# hifiberry_breakout.net
KiCad netlist of a schematic drawn in EAGLE
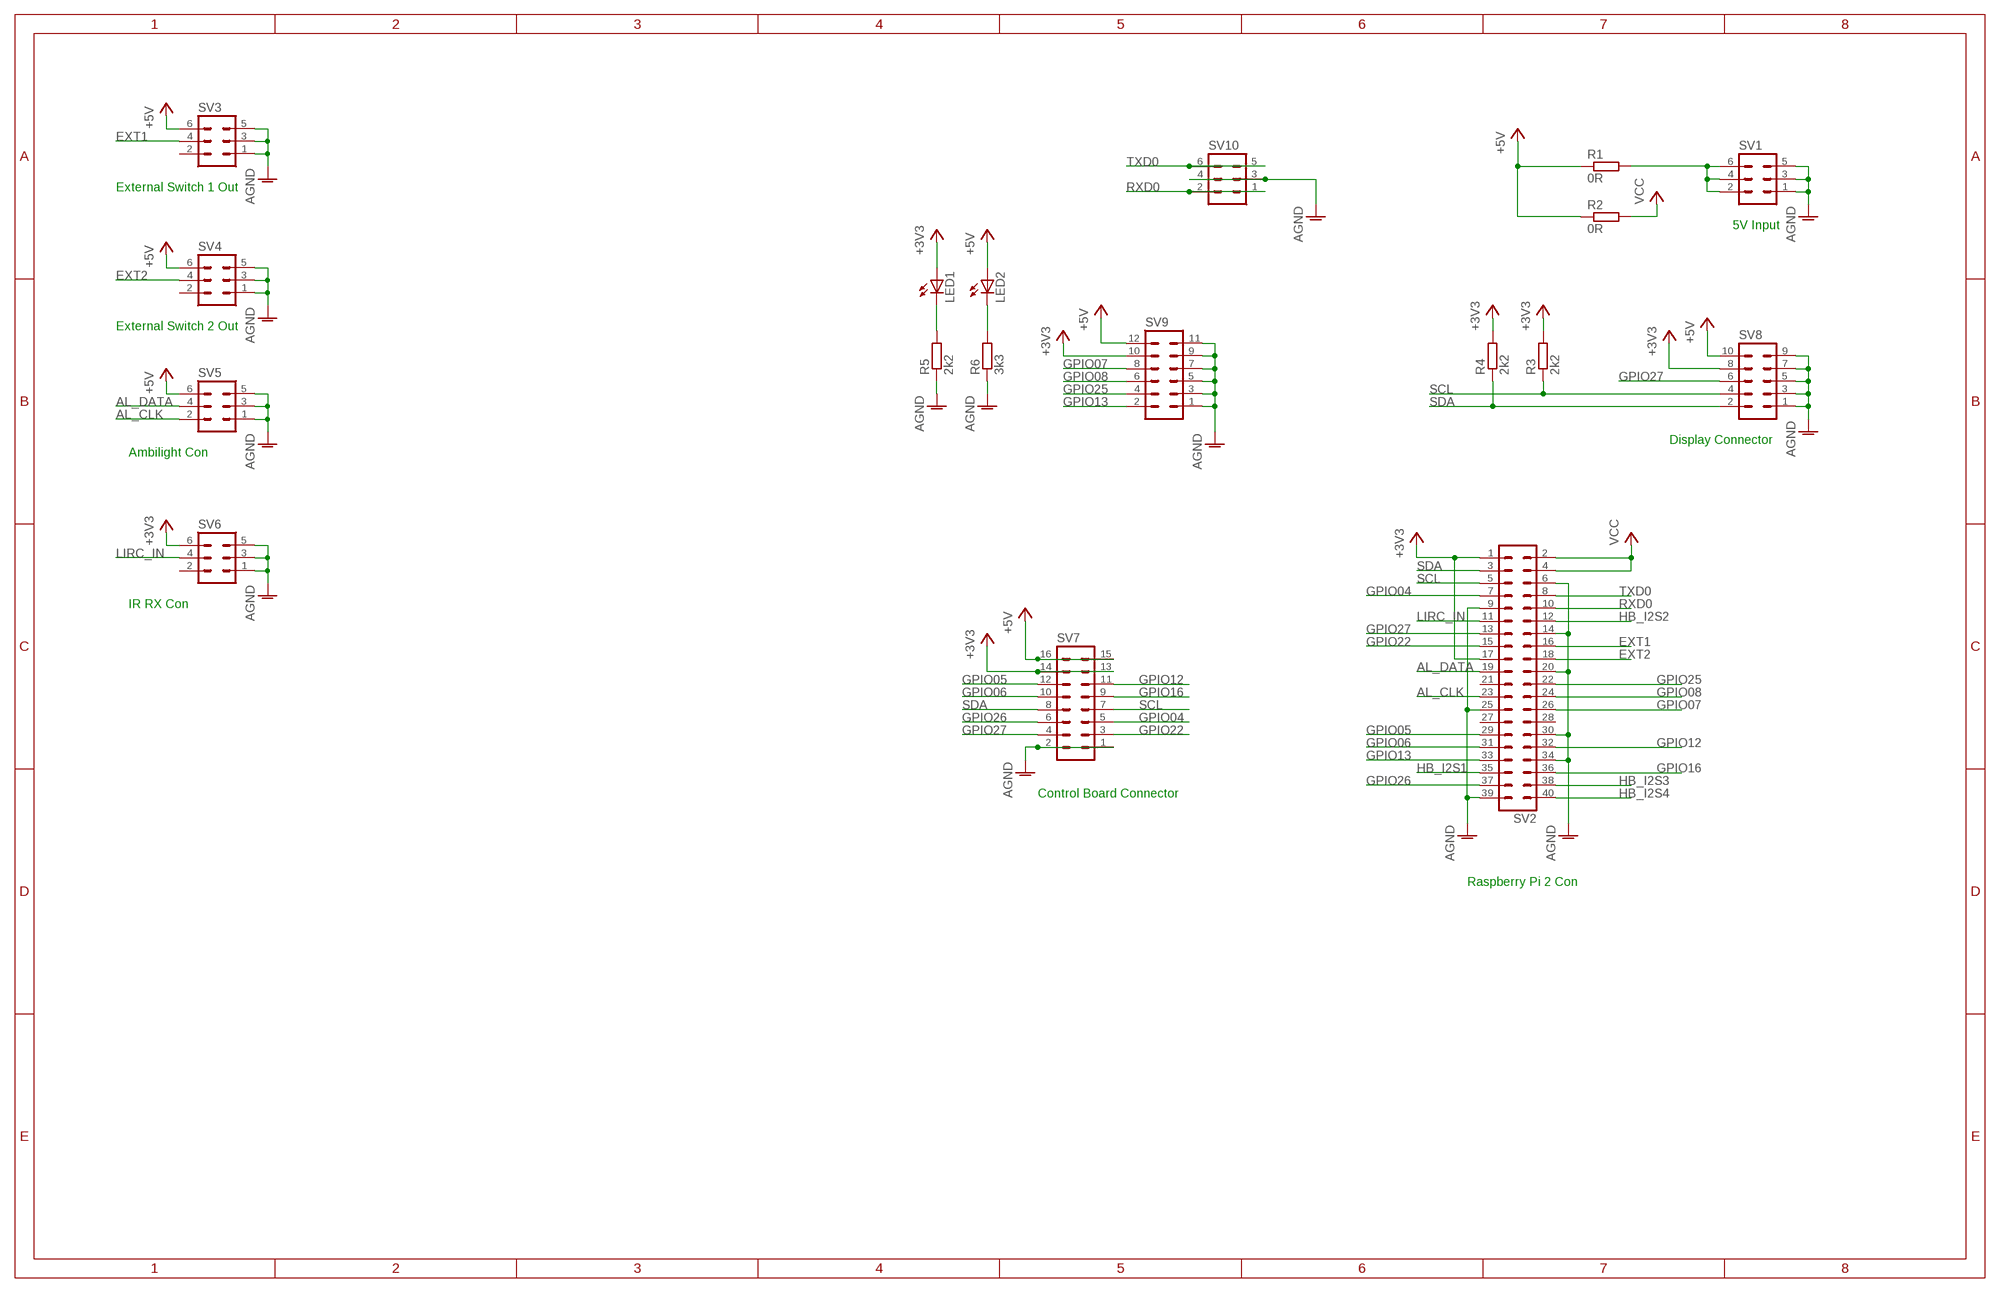
[diagram p0: schematic, sheet 1]

(export (version "E")
  (design (tool "Eeschema 10.0.6"))
  (components
    (comp (ref "LED1")
      (value "LEDCHIPLED_0603")
      (footprint "eagle-import:CHIPLED_0603")
      (libsource (lib "eagle-import") (part "LEDCHIPLED_0603"))
    )
    (comp (ref "LED2")
      (value "LEDCHIPLED_0603")
      (footprint "eagle-import:CHIPLED_0603")
      (libsource (lib "eagle-import") (part "LEDCHIPLED_0603"))
    )
    (comp (ref "R1")
      (value "0R")
      (footprint "eagle-import:R1206")
      (libsource (lib "eagle-import") (part "R-EU_R1206"))
    )
    (comp (ref "R2")
      (value "0R")
      (footprint "eagle-import:R1206")
      (libsource (lib "eagle-import") (part "R-EU_R1206"))
    )
    (comp (ref "R3")
      (value "2k2")
      (footprint "eagle-import:R0603")
      (libsource (lib "eagle-import") (part "R-EU_R0603"))
    )
    (comp (ref "R4")
      (value "2k2")
      (footprint "eagle-import:R0603")
      (libsource (lib "eagle-import") (part "R-EU_R0603"))
    )
    (comp (ref "R5")
      (value "2k2")
      (footprint "eagle-import:R0603")
      (libsource (lib "eagle-import") (part "R-EU_R0603"))
    )
    (comp (ref "R6")
      (value "3k3")
      (footprint "eagle-import:R0603")
      (libsource (lib "eagle-import") (part "R-EU_R0603"))
    )
    (comp (ref "SV1")
      (value "MA03-2")
      (footprint "eagle-import:MA03-2")
      (libsource (lib "eagle-import") (part "MA03-2"))
    )
    (comp (ref "SV2")
      (value "MA20-2")
      (footprint "eagle-import:MA20-2")
      (libsource (lib "eagle-import") (part "MA20-2"))
    )
    (comp (ref "SV3")
      (value "MA03-2")
      (footprint "eagle-import:MA03-2")
      (libsource (lib "eagle-import") (part "MA03-2"))
    )
    (comp (ref "SV4")
      (value "MA03-2")
      (footprint "eagle-import:MA03-2")
      (libsource (lib "eagle-import") (part "MA03-2"))
    )
    (comp (ref "SV5")
      (value "MA03-2")
      (footprint "eagle-import:MA03-2")
      (libsource (lib "eagle-import") (part "MA03-2"))
    )
    (comp (ref "SV6")
      (value "MA03-2")
      (footprint "eagle-import:MA03-2")
      (libsource (lib "eagle-import") (part "MA03-2"))
    )
    (comp (ref "SV7")
      (value "MA08-2")
      (footprint "eagle-import:MA08-2")
      (libsource (lib "eagle-import") (part "MA08-2"))
    )
    (comp (ref "SV8")
      (value "MA05-2")
      (footprint "eagle-import:MA05-2")
      (libsource (lib "eagle-import") (part "MA05-2"))
    )
    (comp (ref "SV9")
      (value "MA06-2")
      (footprint "eagle-import:MA06-2")
      (libsource (lib "eagle-import") (part "MA06-2"))
    )
    (comp (ref "SV10")
      (value "MA03-2")
      (footprint "eagle-import:MA03-2")
      (libsource (lib "eagle-import") (part "MA03-2"))
    )
  )
  (nets
    (net (code "1") (name "+3V3") (class "Default")
      (node (ref "LED1") (pin "A") (pinfunction "A_A") (pintype "passive"))
      (node (ref "R3") (pin "2") (pinfunction "2_2") (pintype "passive"))
      (node (ref "R4") (pin "2") (pinfunction "2_2") (pintype "passive"))
      (node (ref "SV2") (pin "1") (pinfunction "1_1") (pintype "passive"))
      (node (ref "SV2") (pin "17") (pinfunction "17_17") (pintype "passive"))
      (node (ref "SV6") (pin "6") (pinfunction "6_6") (pintype "passive"))
      (node (ref "SV7") (pin "13") (pinfunction "13_13") (pintype "passive"))
      (node (ref "SV7") (pin "14") (pinfunction "14_14") (pintype "passive"))
      (node (ref "SV8") (pin "8") (pinfunction "8_8") (pintype "passive"))
      (node (ref "SV9") (pin "10") (pinfunction "10_10") (pintype "passive"))
    )
    (net (code "2") (name "+5V") (class "Default")
      (node (ref "LED2") (pin "A") (pinfunction "A_A") (pintype "passive"))
      (node (ref "R1") (pin "1") (pinfunction "1_1") (pintype "passive"))
      (node (ref "R2") (pin "1") (pinfunction "1_1") (pintype "passive"))
      (node (ref "SV3") (pin "6") (pinfunction "6_6") (pintype "passive"))
      (node (ref "SV4") (pin "6") (pinfunction "6_6") (pintype "passive"))
      (node (ref "SV5") (pin "6") (pinfunction "6_6") (pintype "passive"))
      (node (ref "SV7") (pin "15") (pinfunction "15_15") (pintype "passive"))
      (node (ref "SV7") (pin "16") (pinfunction "16_16") (pintype "passive"))
      (node (ref "SV8") (pin "10") (pinfunction "10_10") (pintype "passive"))
      (node (ref "SV9") (pin "12") (pinfunction "12_12") (pintype "passive"))
    )
    (net (code "3") (name "/AL_CLK") (class "Default")
      (node (ref "SV2") (pin "23") (pinfunction "23_23") (pintype "passive"))
      (node (ref "SV5") (pin "2") (pinfunction "2_2") (pintype "passive"))
    )
    (net (code "4") (name "/AL_DATA") (class "Default")
      (node (ref "SV2") (pin "19") (pinfunction "19_19") (pintype "passive"))
      (node (ref "SV5") (pin "4") (pinfunction "4_4") (pintype "passive"))
    )
    (net (code "5") (name "/EXT1") (class "Default")
      (node (ref "SV2") (pin "16") (pinfunction "16_16") (pintype "passive"))
      (node (ref "SV3") (pin "4") (pinfunction "4_4") (pintype "passive"))
    )
    (net (code "6") (name "/EXT2") (class "Default")
      (node (ref "SV2") (pin "18") (pinfunction "18_18") (pintype "passive"))
      (node (ref "SV4") (pin "4") (pinfunction "4_4") (pintype "passive"))
    )
    (net (code "7") (name "/GPIO04") (class "Default")
      (node (ref "SV2") (pin "7") (pinfunction "7_7") (pintype "passive"))
      (node (ref "SV7") (pin "5") (pinfunction "5_5") (pintype "passive"))
    )
    (net (code "8") (name "/GPIO05") (class "Default")
      (node (ref "SV2") (pin "29") (pinfunction "29_29") (pintype "passive"))
      (node (ref "SV7") (pin "12") (pinfunction "12_12") (pintype "passive"))
    )
    (net (code "9") (name "/GPIO06") (class "Default")
      (node (ref "SV2") (pin "31") (pinfunction "31_31") (pintype "passive"))
      (node (ref "SV7") (pin "10") (pinfunction "10_10") (pintype "passive"))
    )
    (net (code "10") (name "/GPIO07") (class "Default")
      (node (ref "SV2") (pin "26") (pinfunction "26_26") (pintype "passive"))
      (node (ref "SV9") (pin "8") (pinfunction "8_8") (pintype "passive"))
    )
    (net (code "11") (name "/GPIO08") (class "Default")
      (node (ref "SV2") (pin "24") (pinfunction "24_24") (pintype "passive"))
      (node (ref "SV9") (pin "6") (pinfunction "6_6") (pintype "passive"))
    )
    (net (code "12") (name "/GPIO12") (class "Default")
      (node (ref "SV2") (pin "32") (pinfunction "32_32") (pintype "passive"))
      (node (ref "SV7") (pin "11") (pinfunction "11_11") (pintype "passive"))
    )
    (net (code "13") (name "/GPIO13") (class "Default")
      (node (ref "SV2") (pin "33") (pinfunction "33_33") (pintype "passive"))
      (node (ref "SV9") (pin "2") (pinfunction "2_2") (pintype "passive"))
    )
    (net (code "14") (name "/GPIO16") (class "Default")
      (node (ref "SV2") (pin "36") (pinfunction "36_36") (pintype "passive"))
      (node (ref "SV7") (pin "9") (pinfunction "9_9") (pintype "passive"))
    )
    (net (code "15") (name "/GPIO22") (class "Default")
      (node (ref "SV2") (pin "15") (pinfunction "15_15") (pintype "passive"))
      (node (ref "SV7") (pin "3") (pinfunction "3_3") (pintype "passive"))
    )
    (net (code "16") (name "/GPIO25") (class "Default")
      (node (ref "SV2") (pin "22") (pinfunction "22_22") (pintype "passive"))
      (node (ref "SV9") (pin "4") (pinfunction "4_4") (pintype "passive"))
    )
    (net (code "17") (name "/GPIO26") (class "Default")
      (node (ref "SV2") (pin "37") (pinfunction "37_37") (pintype "passive"))
      (node (ref "SV7") (pin "6") (pinfunction "6_6") (pintype "passive"))
    )
    (net (code "18") (name "/GPIO27") (class "Default")
      (node (ref "SV2") (pin "13") (pinfunction "13_13") (pintype "passive"))
      (node (ref "SV7") (pin "4") (pinfunction "4_4") (pintype "passive"))
      (node (ref "SV8") (pin "6") (pinfunction "6_6") (pintype "passive"))
    )
    (net (code "19") (name "/HB_I2S1") (class "Default")
      (node (ref "SV2") (pin "35") (pinfunction "35_35") (pintype "passive"))
    )
    (net (code "20") (name "/HB_I2S2") (class "Default")
      (node (ref "SV2") (pin "12") (pinfunction "12_12") (pintype "passive"))
    )
    (net (code "21") (name "/HB_I2S3") (class "Default")
      (node (ref "SV2") (pin "38") (pinfunction "38_38") (pintype "passive"))
    )
    (net (code "22") (name "/HB_I2S4") (class "Default")
      (node (ref "SV2") (pin "40") (pinfunction "40_40") (pintype "passive"))
    )
    (net (code "23") (name "/LIRC_IN") (class "Default")
      (node (ref "SV2") (pin "11") (pinfunction "11_11") (pintype "passive"))
      (node (ref "SV6") (pin "4") (pinfunction "4_4") (pintype "passive"))
    )
    (net (code "24") (name "/RXD0") (class "Default")
      (node (ref "SV10") (pin "1") (pinfunction "1_1") (pintype "passive"))
      (node (ref "SV10") (pin "2") (pinfunction "2_2") (pintype "passive"))
      (node (ref "SV2") (pin "10") (pinfunction "10_10") (pintype "passive"))
    )
    (net (code "25") (name "/SCL") (class "Default")
      (node (ref "R3") (pin "1") (pinfunction "1_1") (pintype "passive"))
      (node (ref "SV2") (pin "5") (pinfunction "5_5") (pintype "passive"))
      (node (ref "SV7") (pin "7") (pinfunction "7_7") (pintype "passive"))
      (node (ref "SV8") (pin "4") (pinfunction "4_4") (pintype "passive"))
    )
    (net (code "26") (name "/SDA") (class "Default")
      (node (ref "R4") (pin "1") (pinfunction "1_1") (pintype "passive"))
      (node (ref "SV2") (pin "3") (pinfunction "3_3") (pintype "passive"))
      (node (ref "SV7") (pin "8") (pinfunction "8_8") (pintype "passive"))
      (node (ref "SV8") (pin "2") (pinfunction "2_2") (pintype "passive"))
    )
    (net (code "27") (name "/TXD0") (class "Default")
      (node (ref "SV10") (pin "5") (pinfunction "5_5") (pintype "passive"))
      (node (ref "SV10") (pin "6") (pinfunction "6_6") (pintype "passive"))
      (node (ref "SV2") (pin "8") (pinfunction "8_8") (pintype "passive"))
    )
    (net (code "28") (name "AGND") (class "Default")
      (node (ref "R5") (pin "1") (pinfunction "1_1") (pintype "passive"))
      (node (ref "R6") (pin "1") (pinfunction "1_1") (pintype "passive"))
      (node (ref "SV1") (pin "1") (pinfunction "1_1") (pintype "passive"))
      (node (ref "SV1") (pin "3") (pinfunction "3_3") (pintype "passive"))
      (node (ref "SV1") (pin "5") (pinfunction "5_5") (pintype "passive"))
      (node (ref "SV10") (pin "3") (pinfunction "3_3") (pintype "passive"))
      (node (ref "SV10") (pin "4") (pinfunction "4_4") (pintype "passive"))
      (node (ref "SV2") (pin "14") (pinfunction "14_14") (pintype "passive"))
      (node (ref "SV2") (pin "20") (pinfunction "20_20") (pintype "passive"))
      (node (ref "SV2") (pin "25") (pinfunction "25_25") (pintype "passive"))
      (node (ref "SV2") (pin "30") (pinfunction "30_30") (pintype "passive"))
      (node (ref "SV2") (pin "34") (pinfunction "34_34") (pintype "passive"))
      (node (ref "SV2") (pin "39") (pinfunction "39_39") (pintype "passive"))
      (node (ref "SV2") (pin "6") (pinfunction "6_6") (pintype "passive"))
      (node (ref "SV2") (pin "9") (pinfunction "9_9") (pintype "passive"))
      (node (ref "SV3") (pin "1") (pinfunction "1_1") (pintype "passive"))
      (node (ref "SV3") (pin "3") (pinfunction "3_3") (pintype "passive"))
      (node (ref "SV3") (pin "5") (pinfunction "5_5") (pintype "passive"))
      (node (ref "SV4") (pin "1") (pinfunction "1_1") (pintype "passive"))
      (node (ref "SV4") (pin "3") (pinfunction "3_3") (pintype "passive"))
      (node (ref "SV4") (pin "5") (pinfunction "5_5") (pintype "passive"))
      (node (ref "SV5") (pin "1") (pinfunction "1_1") (pintype "passive"))
      (node (ref "SV5") (pin "3") (pinfunction "3_3") (pintype "passive"))
      (node (ref "SV5") (pin "5") (pinfunction "5_5") (pintype "passive"))
      (node (ref "SV6") (pin "1") (pinfunction "1_1") (pintype "passive"))
      (node (ref "SV6") (pin "3") (pinfunction "3_3") (pintype "passive"))
      (node (ref "SV6") (pin "5") (pinfunction "5_5") (pintype "passive"))
      (node (ref "SV7") (pin "1") (pinfunction "1_1") (pintype "passive"))
      (node (ref "SV7") (pin "2") (pinfunction "2_2") (pintype "passive"))
      (node (ref "SV8") (pin "1") (pinfunction "1_1") (pintype "passive"))
      (node (ref "SV8") (pin "3") (pinfunction "3_3") (pintype "passive"))
      (node (ref "SV8") (pin "5") (pinfunction "5_5") (pintype "passive"))
      (node (ref "SV8") (pin "7") (pinfunction "7_7") (pintype "passive"))
      (node (ref "SV8") (pin "9") (pinfunction "9_9") (pintype "passive"))
      (node (ref "SV9") (pin "1") (pinfunction "1_1") (pintype "passive"))
      (node (ref "SV9") (pin "11") (pinfunction "11_11") (pintype "passive"))
      (node (ref "SV9") (pin "3") (pinfunction "3_3") (pintype "passive"))
      (node (ref "SV9") (pin "5") (pinfunction "5_5") (pintype "passive"))
      (node (ref "SV9") (pin "7") (pinfunction "7_7") (pintype "passive"))
      (node (ref "SV9") (pin "9") (pinfunction "9_9") (pintype "passive"))
    )
    (net (code "29") (name "Net-(LED1-PadC)") (class "Default")
      (node (ref "LED1") (pin "C") (pinfunction "C_C") (pintype "passive"))
      (node (ref "R5") (pin "2") (pinfunction "2_2") (pintype "passive"))
    )
    (net (code "30") (name "Net-(LED2-PadC)") (class "Default")
      (node (ref "LED2") (pin "C") (pinfunction "C_C") (pintype "passive"))
      (node (ref "R6") (pin "2") (pinfunction "2_2") (pintype "passive"))
    )
    (net (code "31") (name "Net-(R1-Pad2)") (class "Default")
      (node (ref "R1") (pin "2") (pinfunction "2_2") (pintype "passive"))
      (node (ref "SV1") (pin "2") (pinfunction "2_2") (pintype "passive"))
      (node (ref "SV1") (pin "4") (pinfunction "4_4") (pintype "passive"))
      (node (ref "SV1") (pin "6") (pinfunction "6_6") (pintype "passive"))
    )
    (net (code "32") (name "VCC") (class "Default")
      (node (ref "R2") (pin "2") (pinfunction "2_2") (pintype "passive"))
      (node (ref "SV2") (pin "2") (pinfunction "2_2") (pintype "passive"))
      (node (ref "SV2") (pin "4") (pinfunction "4_4") (pintype "passive"))
    )
    (net (code "33") (name "unconnected-(SV2-Pad21)") (class "Default")
      (node (ref "SV2") (pin "21") (pinfunction "21_21") (pintype "passive"))
    )
    (net (code "34") (name "unconnected-(SV2-Pad27)") (class "Default")
      (node (ref "SV2") (pin "27") (pinfunction "27_27") (pintype "passive"))
    )
    (net (code "35") (name "unconnected-(SV2-Pad28)") (class "Default")
      (node (ref "SV2") (pin "28") (pinfunction "28_28") (pintype "passive"))
    )
    (net (code "36") (name "unconnected-(SV3-Pad2)") (class "Default")
      (node (ref "SV3") (pin "2") (pinfunction "2_2") (pintype "passive"))
    )
    (net (code "37") (name "unconnected-(SV4-Pad2)") (class "Default")
      (node (ref "SV4") (pin "2") (pinfunction "2_2") (pintype "passive"))
    )
    (net (code "38") (name "unconnected-(SV6-Pad2)") (class "Default")
      (node (ref "SV6") (pin "2") (pinfunction "2_2") (pintype "passive"))
    )
  )
)
